# wad-pcb.net
KiCad netlist of a schematic drawn in EAGLE
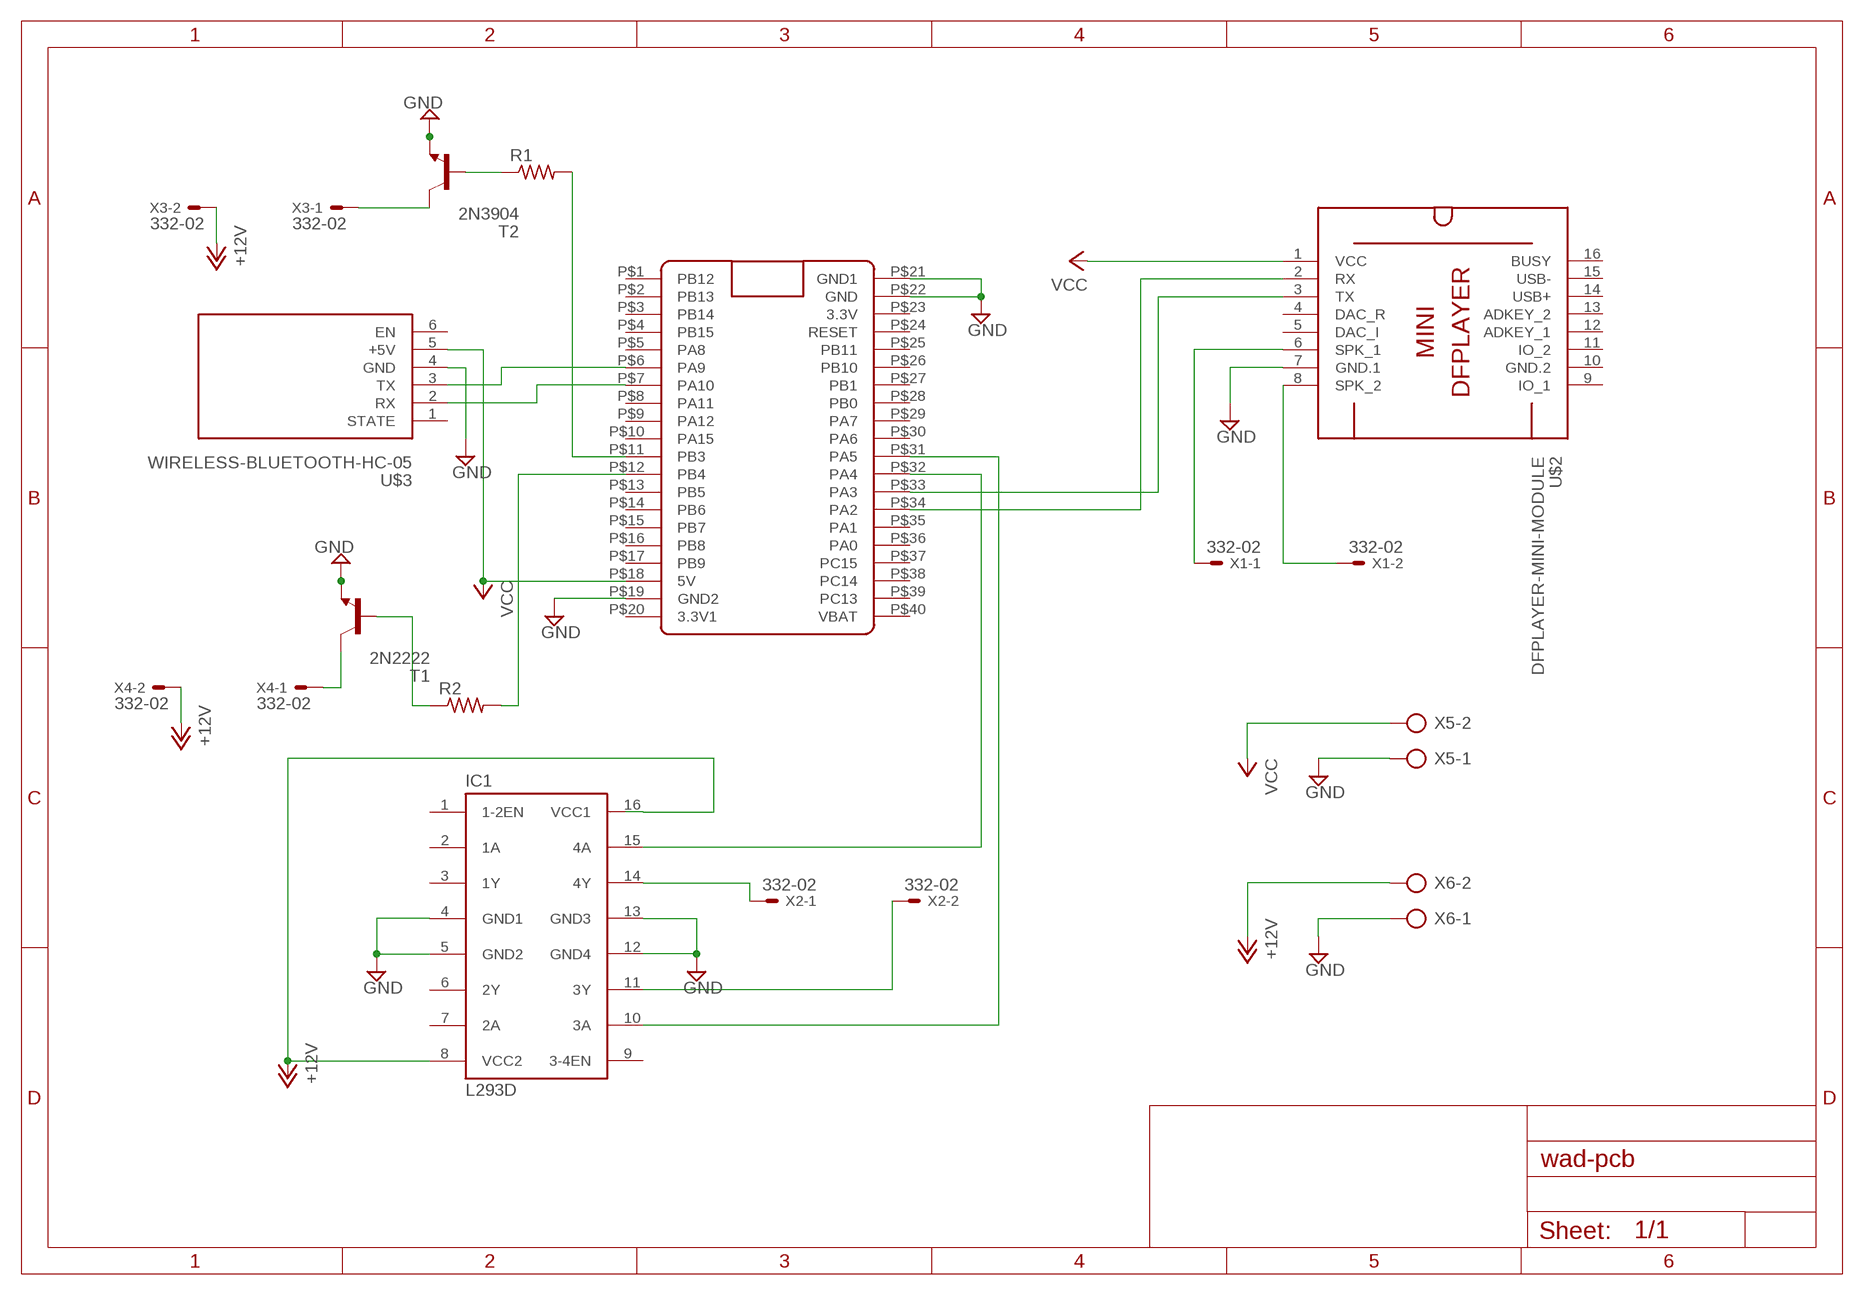
[diagram p0: schematic, sheet 1]

(export (version "E")
  (design (tool "Eeschema 10.0.6"))
  (components
    (comp (ref "IC1")
      (value "L293D")
      (footprint "eagle-import:DIL16")
      (libsource (lib "eagle-import") (part "L293D"))
    )
    (comp (ref "R1")
      (value "R-US_0204/7")
      (footprint "eagle-import:0204_7")
      (libsource (lib "eagle-import") (part "R-US_0204/7"))
    )
    (comp (ref "R2")
      (value "R-US_0204/7")
      (footprint "eagle-import:0204_7")
      (libsource (lib "eagle-import") (part "R-US_0204/7"))
    )
    (comp (ref "T1")
      (value "2N2222")
      (footprint "eagle-import:TO18")
      (libsource (lib "eagle-import") (part "2N2222"))
    )
    (comp (ref "T2")
      (value "2N3904")
      (footprint "eagle-import:TO92")
      (libsource (lib "eagle-import") (part "2N3904"))
    )
    (comp (ref "U$1")
      (value "BLUE_PILL")
      (footprint "eagle-import:BLUE_PILL")
      (libsource (lib "eagle-import") (part "BLUE_PILL"))
    )
    (comp (ref "U$2")
      (value "DFPLAYER-MINI-MODULE")
      (footprint "eagle-import:DFPLAYER-MINI-MODULE")
      (libsource (lib "eagle-import") (part "DFPLAYER-MINI-MODULE"))
    )
    (comp (ref "U$3")
      (value "WIRELESS-BLUETOOTH-HC-05")
      (footprint "eagle-import:WIRELESS-BLUETOOTH-HC-05")
      (libsource (lib "eagle-import") (part "WIRELESS-BLUETOOTH-HC-05"))
    )
    (comp (ref "X1")
      (value "332-02")
      (footprint "eagle-import:332-02")
      (libsource (lib "eagle-import") (part "332-02"))
    )
    (comp (ref "X2")
      (value "332-02")
      (footprint "eagle-import:332-02")
      (libsource (lib "eagle-import") (part "332-02"))
    )
    (comp (ref "X3")
      (value "332-02")
      (footprint "eagle-import:332-02")
      (libsource (lib "eagle-import") (part "332-02"))
    )
    (comp (ref "X4")
      (value "332-02")
      (footprint "eagle-import:332-02")
      (libsource (lib "eagle-import") (part "332-02"))
    )
    (comp (ref "X5")
      (value "AK500/2-H")
      (footprint "eagle-import:AK500_2-H")
      (libsource (lib "eagle-import") (part "AK500/2-H"))
    )
    (comp (ref "X6")
      (value "AK500/2-H")
      (footprint "eagle-import:AK500_2-H")
      (libsource (lib "eagle-import") (part "AK500/2-H"))
    )
  )
  (nets
    (net (code "1") (name "+12V") (class "Default")
      (node (ref "IC1") (pin "16") (pinfunction "VCC1_16") (pintype "power_in"))
      (node (ref "IC1") (pin "8") (pinfunction "VCC2_8") (pintype "power_in"))
      (node (ref "X3") (pin "2") (pinfunction "S_2") (pintype "passive"))
      (node (ref "X4") (pin "2") (pinfunction "S_2") (pintype "passive"))
      (node (ref "X6") (pin "2") (pinfunction "KL_2") (pintype "passive"))
    )
    (net (code "2") (name "/GND.2") (class "Default")
      (node (ref "U$2") (pin "10") (pinfunction "GND.2_10") (pintype "power_in"))
    )
    (net (code "3") (name "GND") (class "Default")
      (node (ref "IC1") (pin "12") (pinfunction "GND4_12") (pintype "power_in"))
      (node (ref "IC1") (pin "13") (pinfunction "GND3_13") (pintype "power_in"))
      (node (ref "IC1") (pin "4") (pinfunction "GND1_4") (pintype "power_in"))
      (node (ref "IC1") (pin "5") (pinfunction "GND2_5") (pintype "power_in"))
      (node (ref "T1") (pin "1") (pinfunction "E_1") (pintype "passive"))
      (node (ref "T2") (pin "3") (pinfunction "E_3") (pintype "passive"))
      (node (ref "U$1") (pin "P$19") (pinfunction "GND2_P$19") (pintype "bidirectional"))
      (node (ref "U$1") (pin "P$21") (pinfunction "GND1_P$21") (pintype "power_in"))
      (node (ref "U$1") (pin "P$22") (pinfunction "GND_P$22") (pintype "bidirectional"))
      (node (ref "U$2") (pin "7") (pinfunction "GND.1_7") (pintype "power_in"))
      (node (ref "U$3") (pin "4") (pinfunction "GND_4") (pintype "power_in"))
      (node (ref "X5") (pin "1") (pinfunction "KL_1") (pintype "passive"))
      (node (ref "X6") (pin "1") (pinfunction "KL_1") (pintype "passive"))
    )
    (net (code "4") (name "Net-(IC1-3A)") (class "Default")
      (node (ref "IC1") (pin "10") (pinfunction "3A_10") (pintype "input"))
      (node (ref "U$1") (pin "P$31") (pinfunction "PA5_P$31") (pintype "bidirectional"))
    )
    (net (code "5") (name "Net-(IC1-3Y)") (class "Default")
      (node (ref "IC1") (pin "11") (pinfunction "3Y_11") (pintype "output"))
      (node (ref "X2") (pin "2") (pinfunction "S_2") (pintype "passive"))
    )
    (net (code "6") (name "Net-(IC1-4A)") (class "Default")
      (node (ref "IC1") (pin "15") (pinfunction "4A_15") (pintype "input"))
      (node (ref "U$1") (pin "P$32") (pinfunction "PA4_P$32") (pintype "bidirectional"))
    )
    (net (code "7") (name "Net-(IC1-4Y)") (class "Default")
      (node (ref "IC1") (pin "14") (pinfunction "4Y_14") (pintype "output"))
      (node (ref "X2") (pin "1") (pinfunction "S_1") (pintype "passive"))
    )
    (net (code "8") (name "Net-(T1-B)") (class "Default")
      (node (ref "R2") (pin "1") (pinfunction "1_1") (pintype "passive"))
      (node (ref "T1") (pin "2") (pinfunction "B_2") (pintype "passive"))
    )
    (net (code "9") (name "Net-(T1-C)") (class "Default")
      (node (ref "T1") (pin "3") (pinfunction "C_3") (pintype "passive"))
      (node (ref "X4") (pin "1") (pinfunction "S_1") (pintype "passive"))
    )
    (net (code "10") (name "Net-(T2-B)") (class "Default")
      (node (ref "R1") (pin "1") (pinfunction "1_1") (pintype "passive"))
      (node (ref "T2") (pin "2") (pinfunction "B_2") (pintype "passive"))
    )
    (net (code "11") (name "Net-(T2-C)") (class "Default")
      (node (ref "T2") (pin "1") (pinfunction "C_1") (pintype "passive"))
      (node (ref "X3") (pin "1") (pinfunction "S_1") (pintype "passive"))
    )
    (net (code "12") (name "Net-(U$1-PA2)") (class "Default")
      (node (ref "U$1") (pin "P$34") (pinfunction "PA2_P$34") (pintype "bidirectional"))
      (node (ref "U$2") (pin "2") (pinfunction "RX_2") (pintype "bidirectional"))
    )
    (net (code "13") (name "Net-(U$1-PA3)") (class "Default")
      (node (ref "U$1") (pin "P$33") (pinfunction "PA3_P$33") (pintype "bidirectional"))
      (node (ref "U$2") (pin "3") (pinfunction "TX_3") (pintype "bidirectional"))
    )
    (net (code "14") (name "Net-(U$1-PA9)") (class "Default")
      (node (ref "U$1") (pin "P$6") (pinfunction "PA9_P$6") (pintype "bidirectional"))
      (node (ref "U$3") (pin "3") (pinfunction "TX_3") (pintype "bidirectional"))
    )
    (net (code "15") (name "Net-(U$1-PA10)") (class "Default")
      (node (ref "U$1") (pin "P$7") (pinfunction "PA10_P$7") (pintype "bidirectional"))
      (node (ref "U$3") (pin "2") (pinfunction "RX_2") (pintype "bidirectional"))
    )
    (net (code "16") (name "Net-(U$1-PB3)") (class "Default")
      (node (ref "R1") (pin "2") (pinfunction "2_2") (pintype "passive"))
      (node (ref "U$1") (pin "P$11") (pinfunction "PB3_P$11") (pintype "bidirectional"))
    )
    (net (code "17") (name "Net-(U$1-PB4)") (class "Default")
      (node (ref "R2") (pin "2") (pinfunction "2_2") (pintype "passive"))
      (node (ref "U$1") (pin "P$12") (pinfunction "PB4_P$12") (pintype "bidirectional"))
    )
    (net (code "18") (name "Net-(U$2-SPK_1)") (class "Default")
      (node (ref "U$2") (pin "6") (pinfunction "SPK_1_6") (pintype "bidirectional"))
      (node (ref "X1") (pin "1") (pinfunction "S_1") (pintype "passive"))
    )
    (net (code "19") (name "Net-(U$2-SPK_2)") (class "Default")
      (node (ref "U$2") (pin "8") (pinfunction "SPK_2_8") (pintype "bidirectional"))
      (node (ref "X1") (pin "2") (pinfunction "S_2") (pintype "passive"))
    )
    (net (code "20") (name "VCC") (class "Default")
      (node (ref "U$1") (pin "P$18") (pinfunction "5V_P$18") (pintype "bidirectional"))
      (node (ref "U$2") (pin "1") (pinfunction "VCC_1") (pintype "power_in"))
      (node (ref "U$3") (pin "5") (pinfunction "+5V_5") (pintype "power_in"))
      (node (ref "X5") (pin "2") (pinfunction "KL_2") (pintype "passive"))
    )
    (net (code "21") (name "unconnected-(IC1-1-2EN-Pad1)") (class "Default")
      (node (ref "IC1") (pin "1") (pinfunction "1-2EN_1") (pintype "input"))
    )
    (net (code "22") (name "unconnected-(IC1-1A-Pad2)") (class "Default")
      (node (ref "IC1") (pin "2") (pinfunction "1A_2") (pintype "input"))
    )
    (net (code "23") (name "unconnected-(IC1-1Y-Pad3)") (class "Default")
      (node (ref "IC1") (pin "3") (pinfunction "1Y_3") (pintype "output"))
    )
    (net (code "24") (name "unconnected-(IC1-2A-Pad7)") (class "Default")
      (node (ref "IC1") (pin "7") (pinfunction "2A_7") (pintype "input"))
    )
    (net (code "25") (name "unconnected-(IC1-2Y-Pad6)") (class "Default")
      (node (ref "IC1") (pin "6") (pinfunction "2Y_6") (pintype "output"))
    )
    (net (code "26") (name "unconnected-(IC1-3-4EN-Pad9)") (class "Default")
      (node (ref "IC1") (pin "9") (pinfunction "3-4EN_9") (pintype "input"))
    )
    (net (code "27") (name "unconnected-(U$1-3.3V-PadP$23)") (class "Default")
      (node (ref "U$1") (pin "P$23") (pinfunction "3.3V_P$23") (pintype "bidirectional"))
    )
    (net (code "28") (name "unconnected-(U$1-3.3V1-PadP$20)") (class "Default")
      (node (ref "U$1") (pin "P$20") (pinfunction "3.3V1_P$20") (pintype "bidirectional"))
    )
    (net (code "29") (name "unconnected-(U$1-PA0-PadP$36)") (class "Default")
      (node (ref "U$1") (pin "P$36") (pinfunction "PA0_P$36") (pintype "bidirectional"))
    )
    (net (code "30") (name "unconnected-(U$1-PA1-PadP$35)") (class "Default")
      (node (ref "U$1") (pin "P$35") (pinfunction "PA1_P$35") (pintype "bidirectional"))
    )
    (net (code "31") (name "unconnected-(U$1-PA6-PadP$30)") (class "Default")
      (node (ref "U$1") (pin "P$30") (pinfunction "PA6_P$30") (pintype "bidirectional"))
    )
    (net (code "32") (name "unconnected-(U$1-PA7-PadP$29)") (class "Default")
      (node (ref "U$1") (pin "P$29") (pinfunction "PA7_P$29") (pintype "bidirectional"))
    )
    (net (code "33") (name "unconnected-(U$1-PA8-PadP$5)") (class "Default")
      (node (ref "U$1") (pin "P$5") (pinfunction "PA8_P$5") (pintype "bidirectional"))
    )
    (net (code "34") (name "unconnected-(U$1-PA11-PadP$8)") (class "Default")
      (node (ref "U$1") (pin "P$8") (pinfunction "PA11_P$8") (pintype "bidirectional"))
    )
    (net (code "35") (name "unconnected-(U$1-PA12-PadP$9)") (class "Default")
      (node (ref "U$1") (pin "P$9") (pinfunction "PA12_P$9") (pintype "bidirectional"))
    )
    (net (code "36") (name "unconnected-(U$1-PA15-PadP$10)") (class "Default")
      (node (ref "U$1") (pin "P$10") (pinfunction "PA15_P$10") (pintype "bidirectional"))
    )
    (net (code "37") (name "unconnected-(U$1-PB0-PadP$28)") (class "Default")
      (node (ref "U$1") (pin "P$28") (pinfunction "PB0_P$28") (pintype "bidirectional"))
    )
    (net (code "38") (name "unconnected-(U$1-PB1-PadP$27)") (class "Default")
      (node (ref "U$1") (pin "P$27") (pinfunction "PB1_P$27") (pintype "bidirectional"))
    )
    (net (code "39") (name "unconnected-(U$1-PB5-PadP$13)") (class "Default")
      (node (ref "U$1") (pin "P$13") (pinfunction "PB5_P$13") (pintype "bidirectional"))
    )
    (net (code "40") (name "unconnected-(U$1-PB6-PadP$14)") (class "Default")
      (node (ref "U$1") (pin "P$14") (pinfunction "PB6_P$14") (pintype "bidirectional"))
    )
    (net (code "41") (name "unconnected-(U$1-PB7-PadP$15)") (class "Default")
      (node (ref "U$1") (pin "P$15") (pinfunction "PB7_P$15") (pintype "bidirectional"))
    )
    (net (code "42") (name "unconnected-(U$1-PB8-PadP$16)") (class "Default")
      (node (ref "U$1") (pin "P$16") (pinfunction "PB8_P$16") (pintype "bidirectional"))
    )
    (net (code "43") (name "unconnected-(U$1-PB9-PadP$17)") (class "Default")
      (node (ref "U$1") (pin "P$17") (pinfunction "PB9_P$17") (pintype "bidirectional"))
    )
    (net (code "44") (name "unconnected-(U$1-PB10-PadP$26)") (class "Default")
      (node (ref "U$1") (pin "P$26") (pinfunction "PB10_P$26") (pintype "bidirectional"))
    )
    (net (code "45") (name "unconnected-(U$1-PB11-PadP$25)") (class "Default")
      (node (ref "U$1") (pin "P$25") (pinfunction "PB11_P$25") (pintype "bidirectional"))
    )
    (net (code "46") (name "unconnected-(U$1-PB12-PadP$1)") (class "Default")
      (node (ref "U$1") (pin "P$1") (pinfunction "PB12_P$1") (pintype "bidirectional"))
    )
    (net (code "47") (name "unconnected-(U$1-PB13-PadP$2)") (class "Default")
      (node (ref "U$1") (pin "P$2") (pinfunction "PB13_P$2") (pintype "bidirectional"))
    )
    (net (code "48") (name "unconnected-(U$1-PB14-PadP$3)") (class "Default")
      (node (ref "U$1") (pin "P$3") (pinfunction "PB14_P$3") (pintype "bidirectional"))
    )
    (net (code "49") (name "unconnected-(U$1-PB15-PadP$4)") (class "Default")
      (node (ref "U$1") (pin "P$4") (pinfunction "PB15_P$4") (pintype "bidirectional"))
    )
    (net (code "50") (name "unconnected-(U$1-PC13-PadP$39)") (class "Default")
      (node (ref "U$1") (pin "P$39") (pinfunction "PC13_P$39") (pintype "bidirectional"))
    )
    (net (code "51") (name "unconnected-(U$1-PC14-PadP$38)") (class "Default")
      (node (ref "U$1") (pin "P$38") (pinfunction "PC14_P$38") (pintype "bidirectional"))
    )
    (net (code "52") (name "unconnected-(U$1-PC15-PadP$37)") (class "Default")
      (node (ref "U$1") (pin "P$37") (pinfunction "PC15_P$37") (pintype "bidirectional"))
    )
    (net (code "53") (name "unconnected-(U$1-RESET-PadP$24)") (class "Default")
      (node (ref "U$1") (pin "P$24") (pinfunction "RESET_P$24") (pintype "bidirectional"))
    )
    (net (code "54") (name "unconnected-(U$1-VBAT-PadP$40)") (class "Default")
      (node (ref "U$1") (pin "P$40") (pinfunction "VBAT_P$40") (pintype "bidirectional"))
    )
    (net (code "55") (name "unconnected-(U$2-ADKEY_1-Pad12)") (class "Default")
      (node (ref "U$2") (pin "12") (pinfunction "ADKEY_1_12") (pintype "bidirectional"))
    )
    (net (code "56") (name "unconnected-(U$2-ADKEY_2-Pad13)") (class "Default")
      (node (ref "U$2") (pin "13") (pinfunction "ADKEY_2_13") (pintype "bidirectional"))
    )
    (net (code "57") (name "unconnected-(U$2-BUSY-Pad16)") (class "Default")
      (node (ref "U$2") (pin "16") (pinfunction "BUSY_16") (pintype "bidirectional"))
    )
    (net (code "58") (name "unconnected-(U$2-DAC_I-Pad5)") (class "Default")
      (node (ref "U$2") (pin "5") (pinfunction "DAC_I_5") (pintype "bidirectional"))
    )
    (net (code "59") (name "unconnected-(U$2-DAC_R-Pad4)") (class "Default")
      (node (ref "U$2") (pin "4") (pinfunction "DAC_R_4") (pintype "bidirectional"))
    )
    (net (code "60") (name "unconnected-(U$2-IO_1-Pad9)") (class "Default")
      (node (ref "U$2") (pin "9") (pinfunction "IO_1_9") (pintype "bidirectional"))
    )
    (net (code "61") (name "unconnected-(U$2-IO_2-Pad11)") (class "Default")
      (node (ref "U$2") (pin "11") (pinfunction "IO_2_11") (pintype "bidirectional"))
    )
    (net (code "62") (name "unconnected-(U$2-USB+-Pad14)") (class "Default")
      (node (ref "U$2") (pin "14") (pinfunction "USB+_14") (pintype "bidirectional"))
    )
    (net (code "63") (name "unconnected-(U$2-USB--Pad15)") (class "Default")
      (node (ref "U$2") (pin "15") (pinfunction "USB-_15") (pintype "bidirectional"))
    )
    (net (code "64") (name "unconnected-(U$3-EN-Pad6)") (class "Default")
      (node (ref "U$3") (pin "6") (pinfunction "EN_6") (pintype "bidirectional"))
    )
    (net (code "65") (name "unconnected-(U$3-STATE-Pad1)") (class "Default")
      (node (ref "U$3") (pin "1") (pinfunction "STATE_1") (pintype "bidirectional"))
    )
  )
)
